# Controladora_60_amp_directa.net
KiCad netlist of a schematic drawn in EAGLE
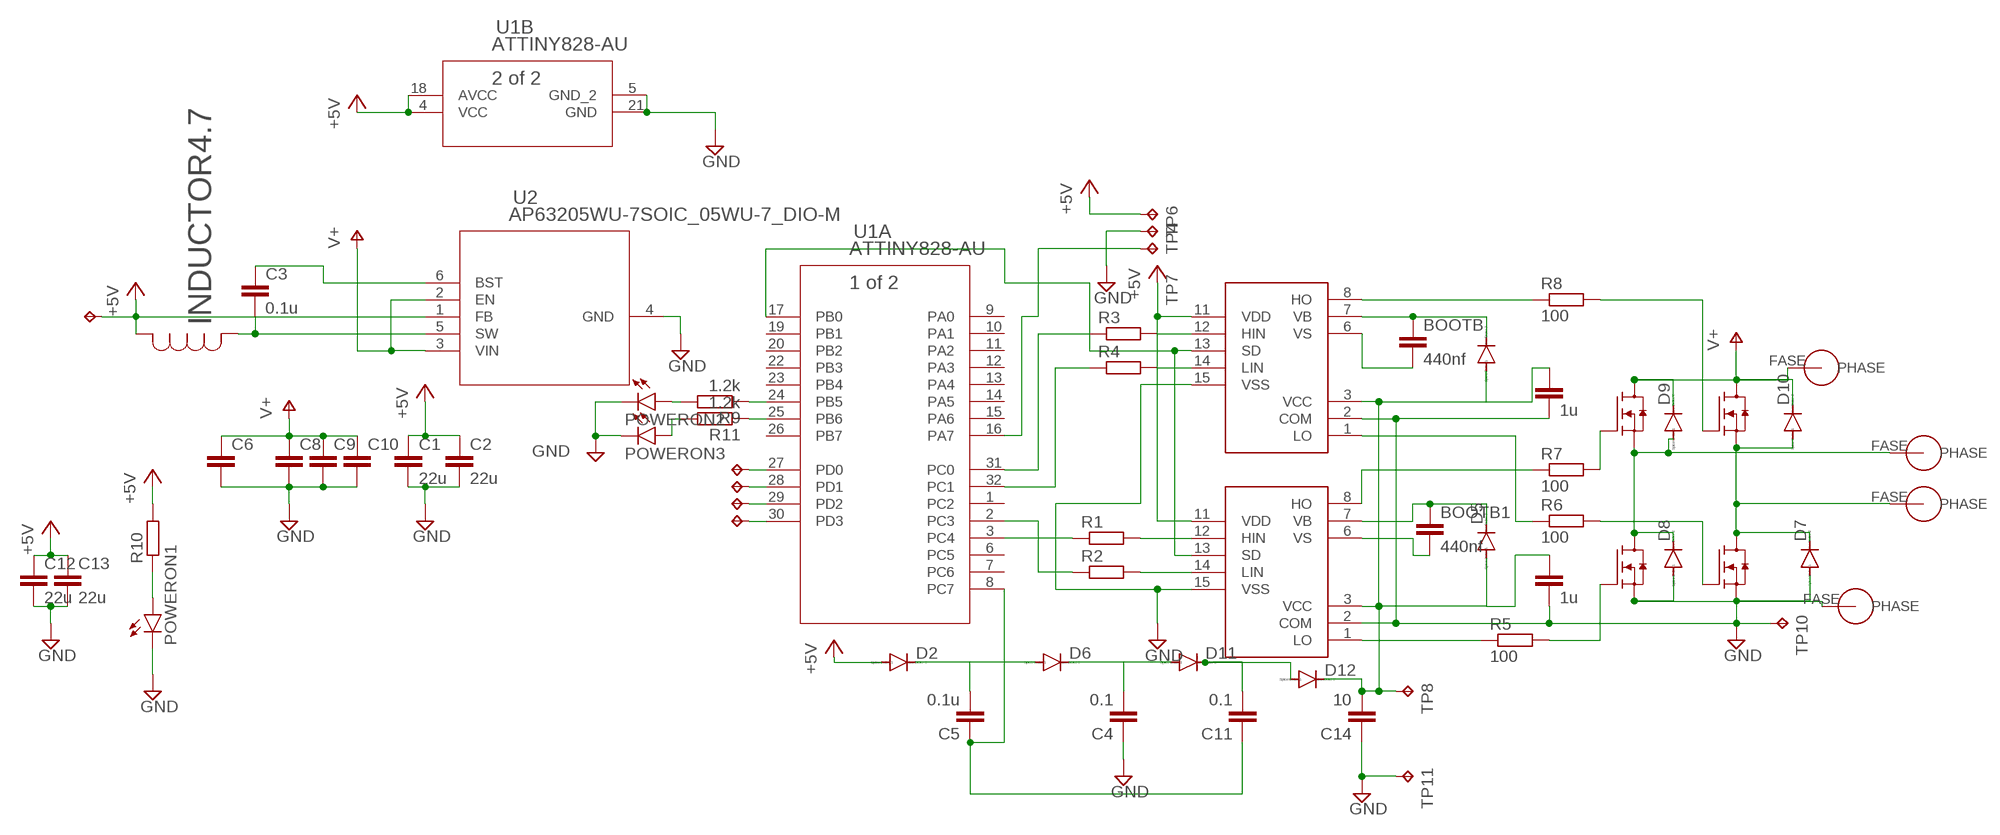
[diagram p0: schematic, sheet 1]

(export (version "E")
  (design (tool "Eeschema 10.0.6"))
  (components
    (comp (ref "BOOTB")
      (value "440nf")
      (footprint "eagle-import:C0805")
      (libsource (lib "eagle-import") (part "resistor_348_C-EUC0805"))
    )
    (comp (ref "BOOTB1")
      (value "440nf")
      (footprint "eagle-import:C0805")
      (libsource (lib "eagle-import") (part "resistor_348_C-EUC0805"))
    )
    (comp (ref "BYPASSBOOT")
      (value "1u")
      (footprint "eagle-import:C0805")
      (libsource (lib "eagle-import") (part "resistor_348_C-EUC0805"))
    )
    (comp (ref "BYPASSBOOT2")
      (value "1u")
      (footprint "eagle-import:C0805")
      (libsource (lib "eagle-import") (part "resistor_348_C-EUC0805"))
    )
    (comp (ref "C1")
      (value "22u")
      (footprint "eagle-import:C0805")
      (libsource (lib "eagle-import") (part "C-EUC0805"))
    )
    (comp (ref "C2")
      (value "22u")
      (footprint "eagle-import:C0805")
      (libsource (lib "eagle-import") (part "C-EUC0805"))
    )
    (comp (ref "C3")
      (value "0.1u")
      (footprint "eagle-import:C0402")
      (libsource (lib "eagle-import") (part "C-EUC0402"))
    )
    (comp (ref "C4")
      (value "0.1")
      (footprint "eagle-import:C0805")
      (libsource (lib "eagle-import") (part "C-EUC0805"))
    )
    (comp (ref "C5")
      (value "0.1u")
      (footprint "eagle-import:C0805")
      (libsource (lib "eagle-import") (part "C-EUC0805"))
    )
    (comp (ref "C6")
      (value "C-EUC0805")
      (footprint "eagle-import:C0805")
      (libsource (lib "eagle-import") (part "C-EUC0805"))
    )
    (comp (ref "C8")
      (value "C-EUC0805")
      (footprint "eagle-import:C0805")
      (libsource (lib "eagle-import") (part "C-EUC0805"))
    )
    (comp (ref "C9")
      (value "C-EU050-035X075")
      (footprint "eagle-import:C050-035X075")
      (libsource (lib "eagle-import") (part "C-EU050-035X075"))
    )
    (comp (ref "C10")
      (value "C-EU050-035X075")
      (footprint "eagle-import:C050-035X075")
      (libsource (lib "eagle-import") (part "C-EU050-035X075"))
    )
    (comp (ref "C11")
      (value "0.1")
      (footprint "eagle-import:C0805")
      (libsource (lib "eagle-import") (part "C-EUC0805"))
    )
    (comp (ref "C12")
      (value "22u")
      (footprint "eagle-import:C0402")
      (libsource (lib "eagle-import") (part "C-EUC0402"))
    )
    (comp (ref "C13")
      (value "22u")
      (footprint "eagle-import:C0402")
      (libsource (lib "eagle-import") (part "C-EUC0402"))
    )
    (comp (ref "C14")
      (value "10")
      (footprint "eagle-import:C0805")
      (libsource (lib "eagle-import") (part "C-EUC0805"))
    )
    (comp (ref "D1")
      (value "IRS2110SPBF")
      (footprint "eagle-import:SOIC127P1030X265-16N")
      (libsource (lib "eagle-import") (part "IRS2110SPBF"))
    )
    (comp (ref "D2")
      (value "DIODE-MINIMELF")
      (footprint "eagle-import:MINIMELF")
      (libsource (lib "eagle-import") (part "DIODE-MINIMELF"))
    )
    (comp (ref "D3")
      (value "IRS2110SPBF")
      (footprint "eagle-import:SOIC127P1030X265-16N")
      (libsource (lib "eagle-import") (part "IRS2110SPBF"))
    )
    (comp (ref "D4")
      (value "DIODE-MINIMELF")
      (footprint "eagle-import:MINIMELF")
      (libsource (lib "eagle-import") (part "DIODE-MINIMELF"))
    )
    (comp (ref "D5")
      (value "DIODE-MINIMELF")
      (footprint "eagle-import:MINIMELF")
      (libsource (lib "eagle-import") (part "DIODE-MINIMELF"))
    )
    (comp (ref "D6")
      (value "DIODE-MINIMELF")
      (footprint "eagle-import:MINIMELF")
      (libsource (lib "eagle-import") (part "DIODE-MINIMELF"))
    )
    (comp (ref "D7")
      (value "DIODE-MINIMELF")
      (footprint "eagle-import:MINIMELF")
      (libsource (lib "eagle-import") (part "DIODE-MINIMELF"))
    )
    (comp (ref "D8")
      (value "DIODE-MINIMELF")
      (footprint "eagle-import:MINIMELF")
      (libsource (lib "eagle-import") (part "DIODE-MINIMELF"))
    )
    (comp (ref "D9")
      (value "DIODE-MINIMELF")
      (footprint "eagle-import:MINIMELF")
      (libsource (lib "eagle-import") (part "DIODE-MINIMELF"))
    )
    (comp (ref "D10")
      (value "DIODE-MINIMELF")
      (footprint "eagle-import:MINIMELF")
      (libsource (lib "eagle-import") (part "DIODE-MINIMELF"))
    )
    (comp (ref "D11")
      (value "DIODE-MINIMELF")
      (footprint "eagle-import:MINIMELF")
      (libsource (lib "eagle-import") (part "DIODE-MINIMELF"))
    )
    (comp (ref "D12")
      (value "DIODE-MINIMELF")
      (footprint "eagle-import:MINIMELF")
      (libsource (lib "eagle-import") (part "DIODE-MINIMELF"))
    )
    (comp (ref "FASEA")
      (value "PHASE")
      (footprint "eagle-import:POWEROUT")
      (libsource (lib "eagle-import") (part "PHASE"))
    )
    (comp (ref "FASEA1")
      (value "PHASE")
      (footprint "eagle-import:POWEROUT")
      (libsource (lib "eagle-import") (part "PHASE"))
    )
    (comp (ref "FASEA2")
      (value "PHASE")
      (footprint "eagle-import:POWEROUT")
      (libsource (lib "eagle-import") (part "PHASE"))
    )
    (comp (ref "FASEA3")
      (value "PHASE")
      (footprint "eagle-import:POWEROUT")
      (libsource (lib "eagle-import") (part "PHASE"))
    )
    (comp (ref "LA")
      (value "IPB180N06S4-H1")
      (footprint "eagle-import:PG-TO263-7-3")
      (libsource (lib "eagle-import") (part "IPB180N06S4-H1"))
    )
    (comp (ref "LA1")
      (value "IPB180N06S4-H1")
      (footprint "eagle-import:PG-TO263-7-3")
      (libsource (lib "eagle-import") (part "IPB180N06S4-H1"))
    )
    (comp (ref "LA2")
      (value "IPB180N06S4-H1")
      (footprint "eagle-import:PG-TO263-7-3")
      (libsource (lib "eagle-import") (part "IPB180N06S4-H1"))
    )
    (comp (ref "LA3")
      (value "IPB180N06S4-H1")
      (footprint "eagle-import:PG-TO263-7-3")
      (libsource (lib "eagle-import") (part "IPB180N06S4-H1"))
    )
    (comp (ref "POWERON1")
      (value "LEDCHIPLED_0603")
      (footprint "eagle-import:CHIPLED_0603")
      (libsource (lib "eagle-import") (part "LEDCHIPLED_0603"))
    )
    (comp (ref "POWERON2")
      (value "LEDCHIPLED_0603")
      (footprint "eagle-import:CHIPLED_0603")
      (libsource (lib "eagle-import") (part "LEDCHIPLED_0603"))
    )
    (comp (ref "POWERON3")
      (value "LEDCHIPLED_0603")
      (footprint "eagle-import:CHIPLED_0603")
      (libsource (lib "eagle-import") (part "LEDCHIPLED_0603"))
    )
    (comp (ref "R1")
      (value "R-EU_M0805")
      (footprint "eagle-import:M0805")
      (libsource (lib "eagle-import") (part "R-EU_M0805"))
    )
    (comp (ref "R2")
      (value "R-EU_M0805")
      (footprint "eagle-import:M0805")
      (libsource (lib "eagle-import") (part "R-EU_M0805"))
    )
    (comp (ref "R3")
      (value "R-EU_M0805")
      (footprint "eagle-import:M0805")
      (libsource (lib "eagle-import") (part "R-EU_M0805"))
    )
    (comp (ref "R4")
      (value "R-EU_M0805")
      (footprint "eagle-import:M0805")
      (libsource (lib "eagle-import") (part "R-EU_M0805"))
    )
    (comp (ref "R5")
      (value "100")
      (footprint "eagle-import:M0805")
      (libsource (lib "eagle-import") (part "R-EU_M0805"))
    )
    (comp (ref "R6")
      (value "100")
      (footprint "eagle-import:M0805")
      (libsource (lib "eagle-import") (part "R-EU_M0805"))
    )
    (comp (ref "R7")
      (value "100")
      (footprint "eagle-import:M0805")
      (libsource (lib "eagle-import") (part "R-EU_M0805"))
    )
    (comp (ref "R8")
      (value "100")
      (footprint "eagle-import:M0805")
      (libsource (lib "eagle-import") (part "R-EU_M0805"))
    )
    (comp (ref "R9")
      (value "1.2k")
      (footprint "eagle-import:M0805")
      (libsource (lib "eagle-import") (part "R-EU_M0805"))
    )
    (comp (ref "R10")
      (value "R-EU_M0805")
      (footprint "eagle-import:M0805")
      (libsource (lib "eagle-import") (part "R-EU_M0805"))
    )
    (comp (ref "R11")
      (value "1.2k")
      (footprint "eagle-import:M0805")
      (libsource (lib "eagle-import") (part "R-EU_M0805"))
    )
    (comp (ref "TP1")
      (value "TPTP16SQ")
      (footprint "eagle-import:TP16SQ")
      (libsource (lib "eagle-import") (part "TPTP16SQ"))
    )
    (comp (ref "TP2")
      (value "TPTP16SQ")
      (footprint "eagle-import:TP16SQ")
      (libsource (lib "eagle-import") (part "TPTP16SQ"))
    )
    (comp (ref "TP3")
      (value "TPTP16SQ")
      (footprint "eagle-import:TP16SQ")
      (libsource (lib "eagle-import") (part "TPTP16SQ"))
    )
    (comp (ref "TP4")
      (value "TPTP16SQ")
      (footprint "eagle-import:TP16SQ")
      (libsource (lib "eagle-import") (part "TPTP16SQ"))
    )
    (comp (ref "TP5")
      (value "TPTP16SQ")
      (footprint "eagle-import:TP16SQ")
      (libsource (lib "eagle-import") (part "TPTP16SQ"))
    )
    (comp (ref "TP6")
      (value "TPTP16SQ")
      (footprint "eagle-import:TP16SQ")
      (libsource (lib "eagle-import") (part "TPTP16SQ"))
    )
    (comp (ref "TP7")
      (value "TPTP16SQ")
      (footprint "eagle-import:TP16SQ")
      (libsource (lib "eagle-import") (part "TPTP16SQ"))
    )
    (comp (ref "TP8")
      (value "TPB1,27")
      (footprint "eagle-import:B1,27")
      (libsource (lib "eagle-import") (part "TPB1,27"))
    )
    (comp (ref "TP9")
      (value "TPB1,27")
      (footprint "eagle-import:B1,27")
      (libsource (lib "eagle-import") (part "TPB1,27"))
    )
    (comp (ref "TP10")
      (value "TPB1,27")
      (footprint "eagle-import:B1,27")
      (libsource (lib "eagle-import") (part "TPB1,27"))
    )
    (comp (ref "TP11")
      (value "TPB1,27")
      (footprint "eagle-import:B1,27")
      (libsource (lib "eagle-import") (part "TPB1,27"))
    )
    (comp (ref "U$1")
      (value "INDUCTOR4.7")
      (footprint "eagle-import:IND_NRS5030T100MMGJ_TAY")
      (libsource (lib "eagle-import") (part "INDUCTOR4.7"))
    )
    (comp (ref "U1")
      (value "ATTINY828-AU")
      (footprint "eagle-import:32A_ATM")
      (libsource (lib "eagle-import") (part "ATTINY828-AU"))
    )
    (comp (ref "U2")
      (value "AP63205WU-7SOIC_05WU-7_DIO-M")
      (footprint "eagle-import:SOIC_05WU-7_DIO-M")
      (fields
        (field (name "MANUFACTURER_PART_NUMBER") "AP63205WU-7")
        (field (name "COPYRIGHT") "Copyright (C) 2018 Accelerated Designs. All rights reserved")
      )
      (libsource (lib "eagle-import") (part "AP63205WU-7SOIC_05WU-7_DIO-M"))
    )
  )
  (nets
    (net (code "1") (name "+5V") (class "Default")
      (node (ref "C1") (pin "1") (pinfunction "1_1") (pintype "passive"))
      (node (ref "C12") (pin "1") (pinfunction "1_1") (pintype "passive"))
      (node (ref "C13") (pin "1") (pinfunction "1_1") (pintype "passive"))
      (node (ref "C2") (pin "1") (pinfunction "1_1") (pintype "passive"))
      (node (ref "D1") (pin "11") (pinfunction "VDD_11") (pintype "bidirectional"))
      (node (ref "D2") (pin "A") (pinfunction "A_A") (pintype "passive"))
      (node (ref "D3") (pin "11") (pinfunction "VDD_11") (pintype "bidirectional"))
      (node (ref "R10") (pin "2") (pinfunction "2_2") (pintype "passive"))
      (node (ref "TP6") (pin "TP") (pinfunction "TP_TP") (pintype "input"))
      (node (ref "TP9") (pin "TP") (pinfunction "TP_TP") (pintype "input"))
      (node (ref "U$1") (pin "1") (pinfunction "1_1") (pintype "passive"))
      (node (ref "U1") (pin "18") (pinfunction "AVCC_18") (pintype "power_in"))
      (node (ref "U1") (pin "4") (pinfunction "VCC_4") (pintype "power_in"))
      (node (ref "U2") (pin "1") (pinfunction "FB_1") (pintype "passive"))
    )
    (net (code "2") (name "GND") (class "Default")
      (node (ref "BYPASSBOOT") (pin "2") (pinfunction "2_2") (pintype "passive"))
      (node (ref "BYPASSBOOT2") (pin "2") (pinfunction "2_2") (pintype "passive"))
      (node (ref "C1") (pin "2") (pinfunction "2_2") (pintype "passive"))
      (node (ref "C10") (pin "2") (pinfunction "2_2") (pintype "passive"))
      (node (ref "C12") (pin "2") (pinfunction "2_2") (pintype "passive"))
      (node (ref "C13") (pin "2") (pinfunction "2_2") (pintype "passive"))
      (node (ref "C14") (pin "1") (pinfunction "1_1") (pintype "passive"))
      (node (ref "C2") (pin "2") (pinfunction "2_2") (pintype "passive"))
      (node (ref "C4") (pin "1") (pinfunction "1_1") (pintype "passive"))
      (node (ref "C6") (pin "2") (pinfunction "2_2") (pintype "passive"))
      (node (ref "C8") (pin "2") (pinfunction "2_2") (pintype "passive"))
      (node (ref "C9") (pin "2") (pinfunction "2_2") (pintype "passive"))
      (node (ref "D1") (pin "15") (pinfunction "VSS_15") (pintype "bidirectional"))
      (node (ref "D1") (pin "2") (pinfunction "COM_2") (pintype "bidirectional"))
      (node (ref "D3") (pin "15") (pinfunction "VSS_15") (pintype "bidirectional"))
      (node (ref "D3") (pin "2") (pinfunction "COM_2") (pintype "bidirectional"))
      (node (ref "D7") (pin "A") (pinfunction "A_A") (pintype "passive"))
      (node (ref "D8") (pin "A") (pinfunction "A_A") (pintype "passive"))
      (node (ref "FASEA3") (pin "FASE") (pinfunction "PHASE_FASE") (pintype "bidirectional"))
      (node (ref "LA1") (pin "2") (pinfunction "S_2") (pintype "passive"))
      (node (ref "LA1") (pin "3") (pinfunction "S_3") (pintype "passive"))
      (node (ref "LA1") (pin "5") (pinfunction "S_5") (pintype "passive"))
      (node (ref "LA1") (pin "6") (pinfunction "S_6") (pintype "passive"))
      (node (ref "LA1") (pin "7") (pinfunction "S_7") (pintype "passive"))
      (node (ref "LA3") (pin "2") (pinfunction "S_2") (pintype "passive"))
      (node (ref "LA3") (pin "3") (pinfunction "S_3") (pintype "passive"))
      (node (ref "LA3") (pin "5") (pinfunction "S_5") (pintype "passive"))
      (node (ref "LA3") (pin "6") (pinfunction "S_6") (pintype "passive"))
      (node (ref "LA3") (pin "7") (pinfunction "S_7") (pintype "passive"))
      (node (ref "POWERON1") (pin "C") (pinfunction "C_C") (pintype "passive"))
      (node (ref "POWERON2") (pin "C") (pinfunction "C_C") (pintype "passive"))
      (node (ref "POWERON3") (pin "C") (pinfunction "C_C") (pintype "passive"))
      (node (ref "TP10") (pin "TP") (pinfunction "TP_TP") (pintype "input"))
      (node (ref "TP11") (pin "TP") (pinfunction "TP_TP") (pintype "input"))
      (node (ref "TP4") (pin "TP") (pinfunction "TP_TP") (pintype "input"))
      (node (ref "U1") (pin "21") (pinfunction "GND_21") (pintype "power_in"))
      (node (ref "U1") (pin "5") (pinfunction "GND_2_5") (pintype "power_in"))
      (node (ref "U2") (pin "4") (pinfunction "GND_4") (pintype "passive"))
    )
    (net (code "3") (name "Net-(C4-Pad2)") (class "Default")
      (node (ref "C4") (pin "2") (pinfunction "2_2") (pintype "passive"))
      (node (ref "D11") (pin "A") (pinfunction "A_A") (pintype "passive"))
      (node (ref "D6") (pin "C") (pinfunction "C_C") (pintype "passive"))
    )
    (net (code "4") (name "Net-(C5-Pad2)") (class "Default")
      (node (ref "C5") (pin "2") (pinfunction "2_2") (pintype "passive"))
      (node (ref "D2") (pin "C") (pinfunction "C_C") (pintype "passive"))
      (node (ref "D6") (pin "A") (pinfunction "A_A") (pintype "passive"))
    )
    (net (code "5") (name "Net-(C11-Pad2)") (class "Default")
      (node (ref "C11") (pin "2") (pinfunction "2_2") (pintype "passive"))
      (node (ref "D11") (pin "C") (pinfunction "C_C") (pintype "passive"))
      (node (ref "D12") (pin "A") (pinfunction "A_A") (pintype "passive"))
    )
    (net (code "6") (name "Net-(D1-HIN)") (class "Default")
      (node (ref "D1") (pin "12") (pinfunction "HIN_12") (pintype "bidirectional"))
      (node (ref "R1") (pin "2") (pinfunction "2_2") (pintype "passive"))
    )
    (net (code "7") (name "Net-(D1-HO)") (class "Default")
      (node (ref "D1") (pin "8") (pinfunction "HO_8") (pintype "bidirectional"))
      (node (ref "R7") (pin "1") (pinfunction "1_1") (pintype "passive"))
    )
    (net (code "8") (name "Net-(D1-LIN)") (class "Default")
      (node (ref "D1") (pin "14") (pinfunction "LIN_14") (pintype "bidirectional"))
      (node (ref "R2") (pin "2") (pinfunction "2_2") (pintype "passive"))
    )
    (net (code "9") (name "Net-(D1-LO)") (class "Default")
      (node (ref "D1") (pin "1") (pinfunction "LO_1") (pintype "bidirectional"))
      (node (ref "R5") (pin "1") (pinfunction "1_1") (pintype "passive"))
    )
    (net (code "10") (name "Net-(D1-SD)") (class "Default")
      (node (ref "D1") (pin "13") (pinfunction "SD_13") (pintype "bidirectional"))
      (node (ref "D3") (pin "13") (pinfunction "SD_13") (pintype "bidirectional"))
      (node (ref "U1") (pin "17") (pinfunction "PB0_17") (pintype "bidirectional"))
    )
    (net (code "11") (name "Net-(D1-VB)") (class "Default")
      (node (ref "BOOTB1") (pin "1") (pinfunction "1_1") (pintype "passive"))
      (node (ref "D1") (pin "7") (pinfunction "VB_7") (pintype "bidirectional"))
      (node (ref "D5") (pin "C") (pinfunction "C_C") (pintype "passive"))
    )
    (net (code "12") (name "Net-(D1-VCC)") (class "Default")
      (node (ref "BYPASSBOOT") (pin "1") (pinfunction "1_1") (pintype "passive"))
      (node (ref "BYPASSBOOT2") (pin "1") (pinfunction "1_1") (pintype "passive"))
      (node (ref "C14") (pin "2") (pinfunction "2_2") (pintype "passive"))
      (node (ref "D1") (pin "3") (pinfunction "VCC_3") (pintype "bidirectional"))
      (node (ref "D12") (pin "C") (pinfunction "C_C") (pintype "passive"))
      (node (ref "D3") (pin "3") (pinfunction "VCC_3") (pintype "bidirectional"))
      (node (ref "D4") (pin "A") (pinfunction "A_A") (pintype "passive"))
      (node (ref "D5") (pin "A") (pinfunction "A_A") (pintype "passive"))
      (node (ref "TP8") (pin "TP") (pinfunction "TP_TP") (pintype "input"))
    )
    (net (code "13") (name "Net-(D1-VS)") (class "Default")
      (node (ref "BOOTB1") (pin "2") (pinfunction "2_2") (pintype "passive"))
      (node (ref "D1") (pin "6") (pinfunction "VS_6") (pintype "bidirectional"))
    )
    (net (code "14") (name "Net-(D3-HIN)") (class "Default")
      (node (ref "D3") (pin "12") (pinfunction "HIN_12") (pintype "bidirectional"))
      (node (ref "R3") (pin "2") (pinfunction "2_2") (pintype "passive"))
    )
    (net (code "15") (name "Net-(D3-HO)") (class "Default")
      (node (ref "D3") (pin "8") (pinfunction "HO_8") (pintype "bidirectional"))
      (node (ref "R8") (pin "1") (pinfunction "1_1") (pintype "passive"))
    )
    (net (code "16") (name "Net-(D3-LIN)") (class "Default")
      (node (ref "D3") (pin "14") (pinfunction "LIN_14") (pintype "bidirectional"))
      (node (ref "R4") (pin "2") (pinfunction "2_2") (pintype "passive"))
    )
    (net (code "17") (name "Net-(D3-LO)") (class "Default")
      (node (ref "D3") (pin "1") (pinfunction "LO_1") (pintype "bidirectional"))
      (node (ref "R6") (pin "1") (pinfunction "1_1") (pintype "passive"))
    )
    (net (code "18") (name "Net-(D3-VB)") (class "Default")
      (node (ref "BOOTB") (pin "1") (pinfunction "1_1") (pintype "passive"))
      (node (ref "D3") (pin "7") (pinfunction "VB_7") (pintype "bidirectional"))
      (node (ref "D4") (pin "C") (pinfunction "C_C") (pintype "passive"))
    )
    (net (code "19") (name "Net-(D3-VS)") (class "Default")
      (node (ref "BOOTB") (pin "2") (pinfunction "2_2") (pintype "passive"))
      (node (ref "D3") (pin "6") (pinfunction "VS_6") (pintype "bidirectional"))
    )
    (net (code "20") (name "Net-(FASEA-PHASE)") (class "Default")
      (node (ref "D8") (pin "C") (pinfunction "C_C") (pintype "passive"))
      (node (ref "D9") (pin "A") (pinfunction "A_A") (pintype "passive"))
      (node (ref "FASEA") (pin "FASE") (pinfunction "PHASE_FASE") (pintype "bidirectional"))
      (node (ref "LA") (pin "2") (pinfunction "S_2") (pintype "passive"))
      (node (ref "LA") (pin "3") (pinfunction "S_3") (pintype "passive"))
      (node (ref "LA") (pin "5") (pinfunction "S_5") (pintype "passive"))
      (node (ref "LA") (pin "6") (pinfunction "S_6") (pintype "passive"))
      (node (ref "LA") (pin "7") (pinfunction "S_7") (pintype "passive"))
      (node (ref "LA1") (pin "8") (pinfunction "D_8") (pintype "passive"))
    )
    (net (code "21") (name "Net-(FASEA1-PHASE)") (class "Default")
      (node (ref "D10") (pin "A") (pinfunction "A_A") (pintype "passive"))
      (node (ref "D7") (pin "C") (pinfunction "C_C") (pintype "passive"))
      (node (ref "FASEA1") (pin "FASE") (pinfunction "PHASE_FASE") (pintype "bidirectional"))
      (node (ref "LA2") (pin "2") (pinfunction "S_2") (pintype "passive"))
      (node (ref "LA2") (pin "3") (pinfunction "S_3") (pintype "passive"))
      (node (ref "LA2") (pin "5") (pinfunction "S_5") (pintype "passive"))
      (node (ref "LA2") (pin "6") (pinfunction "S_6") (pintype "passive"))
      (node (ref "LA2") (pin "7") (pinfunction "S_7") (pintype "passive"))
      (node (ref "LA3") (pin "8") (pinfunction "D_8") (pintype "passive"))
    )
    (net (code "22") (name "Net-(LA-G)") (class "Default")
      (node (ref "LA") (pin "1") (pinfunction "G_1") (pintype "passive"))
      (node (ref "R7") (pin "2") (pinfunction "2_2") (pintype "passive"))
    )
    (net (code "23") (name "Net-(LA1-G)") (class "Default")
      (node (ref "LA1") (pin "1") (pinfunction "G_1") (pintype "passive"))
      (node (ref "R5") (pin "2") (pinfunction "2_2") (pintype "passive"))
    )
    (net (code "24") (name "Net-(LA2-G)") (class "Default")
      (node (ref "LA2") (pin "1") (pinfunction "G_1") (pintype "passive"))
      (node (ref "R8") (pin "2") (pinfunction "2_2") (pintype "passive"))
    )
    (net (code "25") (name "Net-(LA3-G)") (class "Default")
      (node (ref "LA3") (pin "1") (pinfunction "G_1") (pintype "passive"))
      (node (ref "R6") (pin "2") (pinfunction "2_2") (pintype "passive"))
    )
    (net (code "26") (name "Net-(POWERON1-PadA)") (class "Default")
      (node (ref "POWERON1") (pin "A") (pinfunction "A_A") (pintype "passive"))
      (node (ref "R10") (pin "1") (pinfunction "1_1") (pintype "passive"))
    )
    (net (code "27") (name "Net-(POWERON2-PadA)") (class "Default")
      (node (ref "POWERON2") (pin "A") (pinfunction "A_A") (pintype "passive"))
      (node (ref "R9") (pin "2") (pinfunction "2_2") (pintype "passive"))
    )
    (net (code "28") (name "Net-(POWERON3-PadA)") (class "Default")
      (node (ref "POWERON3") (pin "A") (pinfunction "A_A") (pintype "passive"))
      (node (ref "R11") (pin "2") (pinfunction "2_2") (pintype "passive"))
    )
    (net (code "29") (name "Net-(U1A-PA7)") (class "Default")
      (node (ref "TP7") (pin "TP") (pinfunction "TP_TP") (pintype "input"))
      (node (ref "U1") (pin "16") (pinfunction "PA7_16") (pintype "bidirectional"))
    )
    (net (code "30") (name "Net-(U1A-PB5)") (class "Default")
      (node (ref "R9") (pin "1") (pinfunction "1_1") (pintype "passive"))
      (node (ref "U1") (pin "24") (pinfunction "PB5_24") (pintype "bidirectional"))
    )
    (net (code "31") (name "Net-(U1A-PB6)") (class "Default")
      (node (ref "R11") (pin "1") (pinfunction "1_1") (pintype "passive"))
      (node (ref "U1") (pin "25") (pinfunction "PB6_25") (pintype "bidirectional"))
    )
    (net (code "32") (name "Net-(U1A-PC0)") (class "Default")
      (node (ref "R3") (pin "1") (pinfunction "1_1") (pintype "passive"))
      (node (ref "U1") (pin "31") (pinfunction "PC0_31") (pintype "bidirectional"))
    )
    (net (code "33") (name "Net-(U1A-PC1)") (class "Default")
      (node (ref "R4") (pin "1") (pinfunction "1_1") (pintype "passive"))
      (node (ref "U1") (pin "32") (pinfunction "PC1_32") (pintype "bidirectional"))
    )
    (net (code "34") (name "Net-(U1A-PC3)") (class "Default")
      (node (ref "R2") (pin "1") (pinfunction "1_1") (pintype "passive"))
      (node (ref "U1") (pin "2") (pinfunction "PC3_2") (pintype "bidirectional"))
    )
    (net (code "35") (name "Net-(U1A-PC4)") (class "Default")
      (node (ref "R1") (pin "1") (pinfunction "1_1") (pintype "passive"))
      (node (ref "U1") (pin "3") (pinfunction "PC4_3") (pintype "bidirectional"))
    )
    (net (code "36") (name "Net-(U1A-PC7)") (class "Default")
      (node (ref "C11") (pin "1") (pinfunction "1_1") (pintype "passive"))
      (node (ref "C5") (pin "1") (pinfunction "1_1") (pintype "passive"))
      (node (ref "U1") (pin "8") (pinfunction "PC7_8") (pintype "bidirectional"))
    )
    (net (code "37") (name "Net-(U1A-PD0)") (class "Default")
      (node (ref "TP5") (pin "TP") (pinfunction "TP_TP") (pintype "input"))
      (node (ref "U1") (pin "27") (pinfunction "PD0_27") (pintype "bidirectional"))
    )
    (net (code "38") (name "Net-(U1A-PD1)") (class "Default")
      (node (ref "TP1") (pin "TP") (pinfunction "TP_TP") (pintype "input"))
      (node (ref "U1") (pin "28") (pinfunction "PD1_28") (pintype "bidirectional"))
    )
    (net (code "39") (name "Net-(U1A-PD2)") (class "Default")
      (node (ref "TP2") (pin "TP") (pinfunction "TP_TP") (pintype "input"))
      (node (ref "U1") (pin "29") (pinfunction "PD2_29") (pintype "bidirectional"))
    )
    (net (code "40") (name "Net-(U1A-PD3)") (class "Default")
      (node (ref "TP3") (pin "TP") (pinfunction "TP_TP") (pintype "input"))
      (node (ref "U1") (pin "30") (pinfunction "PD3_30") (pintype "bidirectional"))
    )
    (net (code "41") (name "Net-(U2-BST)") (class "Default")
      (node (ref "C3") (pin "1") (pinfunction "1_1") (pintype "passive"))
      (node (ref "U2") (pin "6") (pinfunction "BST_6") (pintype "passive"))
    )
    (net (code "42") (name "Net-(U2-SW)") (class "Default")
      (node (ref "C3") (pin "2") (pinfunction "2_2") (pintype "passive"))
      (node (ref "U$1") (pin "2") (pinfunction "2_2") (pintype "passive"))
      (node (ref "U2") (pin "5") (pinfunction "SW_5") (pintype "passive"))
    )
    (net (code "43") (name "V+") (class "Default")
      (node (ref "C10") (pin "1") (pinfunction "1_1") (pintype "passive"))
      (node (ref "C6") (pin "1") (pinfunction "1_1") (pintype "passive"))
      (node (ref "C8") (pin "1") (pinfunction "1_1") (pintype "passive"))
      (node (ref "C9") (pin "1") (pinfunction "1_1") (pintype "passive"))
      (node (ref "D10") (pin "C") (pinfunction "C_C") (pintype "passive"))
      (node (ref "D9") (pin "C") (pinfunction "C_C") (pintype "passive"))
      (node (ref "FASEA2") (pin "FASE") (pinfunction "PHASE_FASE") (pintype "bidirectional"))
      (node (ref "LA") (pin "8") (pinfunction "D_8") (pintype "passive"))
      (node (ref "LA2") (pin "8") (pinfunction "D_8") (pintype "passive"))
      (node (ref "U2") (pin "2") (pinfunction "EN_2") (pintype "passive"))
      (node (ref "U2") (pin "3") (pinfunction "VIN_3") (pintype "passive"))
    )
    (net (code "44") (name "unconnected-(U1A-PA0-Pad9)") (class "Default")
      (node (ref "U1") (pin "9") (pinfunction "PA0_9") (pintype "bidirectional"))
    )
    (net (code "45") (name "unconnected-(U1A-PA1-Pad10)") (class "Default")
      (node (ref "U1") (pin "10") (pinfunction "PA1_10") (pintype "bidirectional"))
    )
    (net (code "46") (name "unconnected-(U1A-PA2-Pad11)") (class "Default")
      (node (ref "U1") (pin "11") (pinfunction "PA2_11") (pintype "bidirectional"))
    )
    (net (code "47") (name "unconnected-(U1A-PA3-Pad12)") (class "Default")
      (node (ref "U1") (pin "12") (pinfunction "PA3_12") (pintype "bidirectional"))
    )
    (net (code "48") (name "unconnected-(U1A-PA4-Pad13)") (class "Default")
      (node (ref "U1") (pin "13") (pinfunction "PA4_13") (pintype "bidirectional"))
    )
    (net (code "49") (name "unconnected-(U1A-PA5-Pad14)") (class "Default")
      (node (ref "U1") (pin "14") (pinfunction "PA5_14") (pintype "bidirectional"))
    )
    (net (code "50") (name "unconnected-(U1A-PA6-Pad15)") (class "Default")
      (node (ref "U1") (pin "15") (pinfunction "PA6_15") (pintype "bidirectional"))
    )
    (net (code "51") (name "unconnected-(U1A-PB1-Pad19)") (class "Default")
      (node (ref "U1") (pin "19") (pinfunction "PB1_19") (pintype "bidirectional"))
    )
    (net (code "52") (name "unconnected-(U1A-PB2-Pad20)") (class "Default")
      (node (ref "U1") (pin "20") (pinfunction "PB2_20") (pintype "bidirectional"))
    )
    (net (code "53") (name "unconnected-(U1A-PB3-Pad22)") (class "Default")
      (node (ref "U1") (pin "22") (pinfunction "PB3_22") (pintype "bidirectional"))
    )
    (net (code "54") (name "unconnected-(U1A-PB4-Pad23)") (class "Default")
      (node (ref "U1") (pin "23") (pinfunction "PB4_23") (pintype "bidirectional"))
    )
    (net (code "55") (name "unconnected-(U1A-PB7-Pad26)") (class "Default")
      (node (ref "U1") (pin "26") (pinfunction "PB7_26") (pintype "bidirectional"))
    )
    (net (code "56") (name "unconnected-(U1A-PC2-Pad1)") (class "Default")
      (node (ref "U1") (pin "1") (pinfunction "PC2_1") (pintype "bidirectional"))
    )
    (net (code "57") (name "unconnected-(U1A-PC5-Pad6)") (class "Default")
      (node (ref "U1") (pin "6") (pinfunction "PC5_6") (pintype "bidirectional"))
    )
    (net (code "58") (name "unconnected-(U1A-PC6-Pad7)") (class "Default")
      (node (ref "U1") (pin "7") (pinfunction "PC6_7") (pintype "bidirectional"))
    )
  )
)
